# stepper_board.net
KiCad netlist of a schematic drawn in EAGLE
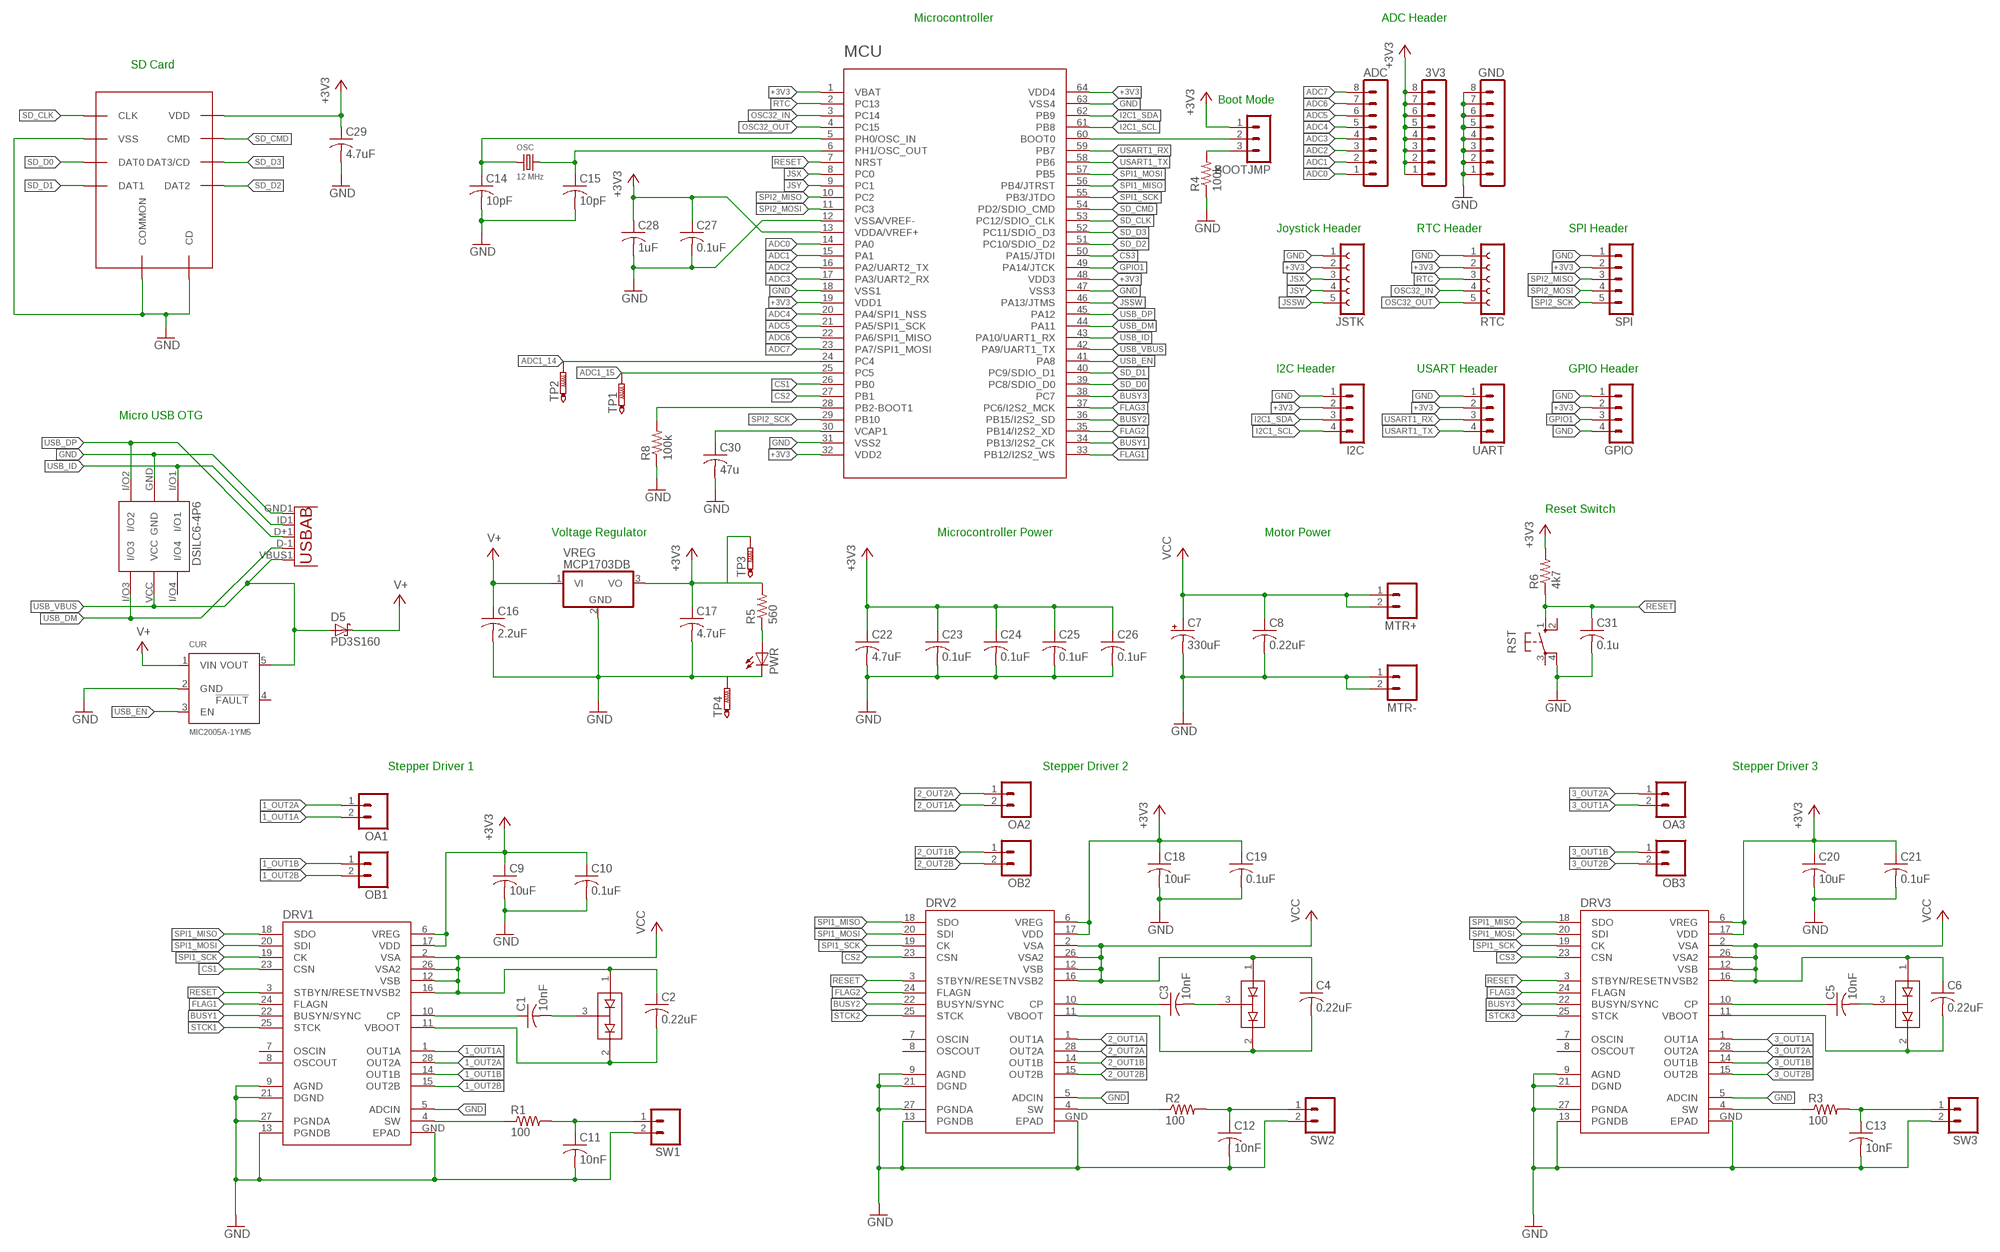
[diagram p0: schematic, sheet 1]

(export (version "E")
  (design (tool "Eeschema 10.0.6"))
  (components
    (comp (ref "3V3")
      (value "MA08-1")
      (footprint "eagle-import:MA08-1")
      (libsource (lib "eagle-import") (part "MA08-1"))
    )
    (comp (ref "ADC")
      (value "MA08-1")
      (footprint "eagle-import:MA08-1")
      (libsource (lib "eagle-import") (part "MA08-1"))
    )
    (comp (ref "BOOTJMP")
      (value "MA03-1")
      (footprint "eagle-import:MA03-1")
      (libsource (lib "eagle-import") (part "MA03-1"))
    )
    (comp (ref "C1")
      (value "10nF")
      (footprint "eagle-import:C0805")
      (libsource (lib "eagle-import") (part "C-USC0805"))
    )
    (comp (ref "C2")
      (value "0.22uF")
      (footprint "eagle-import:C0805")
      (libsource (lib "eagle-import") (part "C-USC0805"))
    )
    (comp (ref "C3")
      (value "10nF")
      (footprint "eagle-import:C0805")
      (libsource (lib "eagle-import") (part "C-USC0805"))
    )
    (comp (ref "C4")
      (value "0.22uF")
      (footprint "eagle-import:C0805")
      (libsource (lib "eagle-import") (part "C-USC0805"))
    )
    (comp (ref "C5")
      (value "10nF")
      (footprint "eagle-import:C0805")
      (libsource (lib "eagle-import") (part "C-USC0805"))
    )
    (comp (ref "C6")
      (value "0.22uF")
      (footprint "eagle-import:C0805")
      (libsource (lib "eagle-import") (part "C-USC0805"))
    )
    (comp (ref "C7")
      (value "330uF")
      (footprint "eagle-import:UD-10X10_NICHICON")
      (libsource (lib "eagle-import") (part "CPOL-USUD-10X10"))
    )
    (comp (ref "C8")
      (value "0.22uF")
      (footprint "eagle-import:C0805")
      (libsource (lib "eagle-import") (part "C-USC0805"))
    )
    (comp (ref "C9")
      (value "10uF")
      (footprint "eagle-import:C0805")
      (libsource (lib "eagle-import") (part "C-USC0805"))
    )
    (comp (ref "C10")
      (value "0.1uF")
      (footprint "eagle-import:C0805")
      (libsource (lib "eagle-import") (part "C-USC0805"))
    )
    (comp (ref "C11")
      (value "10nF")
      (footprint "eagle-import:C0805")
      (libsource (lib "eagle-import") (part "C-USC0805"))
    )
    (comp (ref "C12")
      (value "10nF")
      (footprint "eagle-import:C0805")
      (libsource (lib "eagle-import") (part "C-USC0805"))
    )
    (comp (ref "C13")
      (value "10nF")
      (footprint "eagle-import:C0805")
      (libsource (lib "eagle-import") (part "C-USC0805"))
    )
    (comp (ref "C14")
      (value "10pF")
      (footprint "eagle-import:C0805")
      (libsource (lib "eagle-import") (part "C-USC0805"))
    )
    (comp (ref "C15")
      (value "10pF")
      (footprint "eagle-import:C0805")
      (libsource (lib "eagle-import") (part "C-USC0805"))
    )
    (comp (ref "C16")
      (value "2.2uF")
      (footprint "eagle-import:C0805")
      (libsource (lib "eagle-import") (part "C-USC0805"))
    )
    (comp (ref "C17")
      (value "4.7uF")
      (footprint "eagle-import:C0805")
      (libsource (lib "eagle-import") (part "C-USC0805"))
    )
    (comp (ref "C18")
      (value "10uF")
      (footprint "eagle-import:C0805")
      (libsource (lib "eagle-import") (part "C-USC0805"))
    )
    (comp (ref "C19")
      (value "0.1uF")
      (footprint "eagle-import:C0805")
      (libsource (lib "eagle-import") (part "C-USC0805"))
    )
    (comp (ref "C20")
      (value "10uF")
      (footprint "eagle-import:C0805")
      (libsource (lib "eagle-import") (part "C-USC0805"))
    )
    (comp (ref "C21")
      (value "0.1uF")
      (footprint "eagle-import:C0805")
      (libsource (lib "eagle-import") (part "C-USC0805"))
    )
    (comp (ref "C22")
      (value "4.7uF")
      (footprint "eagle-import:C0805")
      (libsource (lib "eagle-import") (part "C-USC0805"))
    )
    (comp (ref "C23")
      (value "0.1uF")
      (footprint "eagle-import:C0805")
      (libsource (lib "eagle-import") (part "C-USC0805"))
    )
    (comp (ref "C24")
      (value "0.1uF")
      (footprint "eagle-import:C0805")
      (libsource (lib "eagle-import") (part "C-USC0805"))
    )
    (comp (ref "C25")
      (value "0.1uF")
      (footprint "eagle-import:C0805")
      (libsource (lib "eagle-import") (part "C-USC0805"))
    )
    (comp (ref "C26")
      (value "0.1uF")
      (footprint "eagle-import:C0805")
      (libsource (lib "eagle-import") (part "C-USC0805"))
    )
    (comp (ref "C27")
      (value "0.1uF")
      (footprint "eagle-import:C0805")
      (libsource (lib "eagle-import") (part "C-USC0805"))
    )
    (comp (ref "C28")
      (value "1uF")
      (footprint "eagle-import:C0805")
      (libsource (lib "eagle-import") (part "C-USC0805"))
    )
    (comp (ref "C29")
      (value "4.7uF")
      (footprint "eagle-import:C0805")
      (libsource (lib "eagle-import") (part "C-USC0805"))
    )
    (comp (ref "C30")
      (value "47u")
      (footprint "eagle-import:C0805")
      (libsource (lib "eagle-import") (part "C-USC0805"))
    )
    (comp (ref "C31")
      (value "0.1u")
      (footprint "eagle-import:C0805")
      (libsource (lib "eagle-import") (part "C-USC0805"))
    )
    (comp (ref "CUR")
      (value "MIC2005A-1YM5")
      (footprint "eagle-import:SOT23-5")
      (libsource (lib "eagle-import") (part "MIC2005A-1YM5"))
    )
    (comp (ref "D1")
      (value "BAV99")
      (footprint "eagle-import:SOT23")
      (libsource (lib "eagle-import") (part "BAV99"))
    )
    (comp (ref "D2")
      (value "BAV99")
      (footprint "eagle-import:SOT23")
      (libsource (lib "eagle-import") (part "BAV99"))
    )
    (comp (ref "D3")
      (value "BAV99")
      (footprint "eagle-import:SOT23")
      (libsource (lib "eagle-import") (part "BAV99"))
    )
    (comp (ref "D5")
      (value "PD3S160")
      (footprint "eagle-import:POWERDI323")
      (libsource (lib "eagle-import") (part "PD3S160"))
    )
    (comp (ref "DRV1")
      (value "L6470")
      (footprint "eagle-import:HTSSOP28-NOPAD")
      (libsource (lib "eagle-import") (part "L6470"))
    )
    (comp (ref "DRV2")
      (value "L6470")
      (footprint "eagle-import:HTSSOP28-NOPAD")
      (libsource (lib "eagle-import") (part "L6470"))
    )
    (comp (ref "DRV3")
      (value "L6470")
      (footprint "eagle-import:HTSSOP28-NOPAD")
      (libsource (lib "eagle-import") (part "L6470"))
    )
    (comp (ref "ESD")
      (value "DSILC6-4P6")
      (footprint "eagle-import:SOT-666")
      (libsource (lib "eagle-import") (part "DSILC6-4P6"))
    )
    (comp (ref "GND")
      (value "MA08-1")
      (footprint "eagle-import:MA08-1")
      (libsource (lib "eagle-import") (part "MA08-1"))
    )
    (comp (ref "GPIO")
      (value "MA04-1")
      (footprint "eagle-import:MA04-1")
      (libsource (lib "eagle-import") (part "MA04-1"))
    )
    (comp (ref "I2C")
      (value "MA04-1")
      (footprint "eagle-import:MA04-1")
      (libsource (lib "eagle-import") (part "MA04-1"))
    )
    (comp (ref "JSTK")
      (value "FE05-1")
      (footprint "eagle-import:FE05-1")
      (libsource (lib "eagle-import") (part "FE05-1"))
    )
    (comp (ref "MCU")
      (value "STM32F411RE")
      (footprint "eagle-import:TQFP64")
      (libsource (lib "eagle-import") (part "STM32F411RE"))
    )
    (comp (ref "MICROSD")
      (value "SCHA5B0200")
      (footprint "eagle-import:SCHA5B0200")
      (libsource (lib "eagle-import") (part "SCHA5B0200"))
    )
    (comp (ref "MTR+")
      (value "M02")
      (footprint "eagle-import:02P")
      (libsource (lib "eagle-import") (part "M02"))
    )
    (comp (ref "MTR-")
      (value "M02")
      (footprint "eagle-import:02P")
      (libsource (lib "eagle-import") (part "M02"))
    )
    (comp (ref "OA1")
      (value "M02")
      (footprint "eagle-import:02P")
      (libsource (lib "eagle-import") (part "M02"))
    )
    (comp (ref "OA2")
      (value "M02")
      (footprint "eagle-import:02P")
      (libsource (lib "eagle-import") (part "M02"))
    )
    (comp (ref "OA3")
      (value "M02")
      (footprint "eagle-import:02P")
      (libsource (lib "eagle-import") (part "M02"))
    )
    (comp (ref "OB1")
      (value "M02")
      (footprint "eagle-import:02P")
      (libsource (lib "eagle-import") (part "M02"))
    )
    (comp (ref "OB2")
      (value "M02")
      (footprint "eagle-import:02P")
      (libsource (lib "eagle-import") (part "M02"))
    )
    (comp (ref "OB3")
      (value "M02")
      (footprint "eagle-import:02P")
      (libsource (lib "eagle-import") (part "M02"))
    )
    (comp (ref "OSC")
      (value "12 MHz")
      (footprint "eagle-import:3.2X2.5MM")
      (libsource (lib "eagle-import") (part "CRYSTAL.3.2X2.5MM"))
    )
    (comp (ref "PWR")
      (value "LEDCHIP-LED0805")
      (footprint "eagle-import:CHIP-LED0805")
      (libsource (lib "eagle-import") (part "LEDCHIP-LED0805"))
    )
    (comp (ref "R1")
      (value "100")
      (footprint "eagle-import:R0805")
      (libsource (lib "eagle-import") (part "resistor_R-US_R0805"))
    )
    (comp (ref "R2")
      (value "100")
      (footprint "eagle-import:R0805")
      (libsource (lib "eagle-import") (part "resistor_R-US_R0805"))
    )
    (comp (ref "R3")
      (value "100")
      (footprint "eagle-import:R0805")
      (libsource (lib "eagle-import") (part "resistor_R-US_R0805"))
    )
    (comp (ref "R4")
      (value "100k")
      (footprint "eagle-import:R0805")
      (libsource (lib "eagle-import") (part "R-US_R0805"))
    )
    (comp (ref "R5")
      (value "560")
      (footprint "eagle-import:R0805")
      (libsource (lib "eagle-import") (part "R-US_R0805"))
    )
    (comp (ref "R6")
      (value "4k7")
      (footprint "eagle-import:R0805")
      (libsource (lib "eagle-import") (part "R-US_R0805"))
    )
    (comp (ref "R8")
      (value "100k")
      (footprint "eagle-import:R0805")
      (libsource (lib "eagle-import") (part "R-US_R0805"))
    )
    (comp (ref "RST")
      (value "10-XX")
      (footprint "eagle-import:B3F-10XX")
      (fields (field (name "MPN") "B3F-1000"))
      (libsource (lib "eagle-import") (part "10-XX"))
    )
    (comp (ref "RTC")
      (value "FE05-1")
      (footprint "eagle-import:FE05-1")
      (libsource (lib "eagle-import") (part "FE05-1"))
    )
    (comp (ref "SPI")
      (value "MA05-1")
      (footprint "eagle-import:MA05-1")
      (libsource (lib "eagle-import") (part "MA05-1"))
    )
    (comp (ref "SW1")
      (value "M02")
      (footprint "eagle-import:02P")
      (libsource (lib "eagle-import") (part "M02"))
    )
    (comp (ref "SW2")
      (value "M02")
      (footprint "eagle-import:02P")
      (libsource (lib "eagle-import") (part "M02"))
    )
    (comp (ref "SW3")
      (value "M02")
      (footprint "eagle-import:02P")
      (libsource (lib "eagle-import") (part "M02"))
    )
    (comp (ref "TP1")
      (value "PTR1B1,27")
      (footprint "eagle-import:B1,27")
      (libsource (lib "eagle-import") (part "PTR1B1,27"))
    )
    (comp (ref "TP2")
      (value "PTR1B1,27")
      (footprint "eagle-import:B1,27")
      (libsource (lib "eagle-import") (part "PTR1B1,27"))
    )
    (comp (ref "TP3")
      (value "PTR1B1,27")
      (footprint "eagle-import:B1,27")
      (libsource (lib "eagle-import") (part "PTR1B1,27"))
    )
    (comp (ref "TP4")
      (value "PTR1B1,27")
      (footprint "eagle-import:B1,27")
      (libsource (lib "eagle-import") (part "PTR1B1,27"))
    )
    (comp (ref "UART")
      (value "MA04-1")
      (footprint "eagle-import:MA04-1")
      (libsource (lib "eagle-import") (part "MA04-1"))
    )
    (comp (ref "USB")
      (value "USB\"\"")
      (footprint "eagle-import:USB-MICRO-SMD")
      (libsource (lib "eagle-import") (part "USB{dblquote}{dblquote}"))
    )
    (comp (ref "VREG")
      (value "MCP1703DB")
      (footprint "eagle-import:SOT223")
      (libsource (lib "eagle-import") (part "MCP1703DB"))
    )
  )
  (nets
    (net (code "1") (name "+3V3") (class "Default")
      (node (ref "3V3") (pin "1") (pinfunction "1_1") (pintype "passive"))
      (node (ref "3V3") (pin "2") (pinfunction "2_2") (pintype "passive"))
      (node (ref "3V3") (pin "3") (pinfunction "3_3") (pintype "passive"))
      (node (ref "3V3") (pin "4") (pinfunction "4_4") (pintype "passive"))
      (node (ref "3V3") (pin "5") (pinfunction "5_5") (pintype "passive"))
      (node (ref "3V3") (pin "6") (pinfunction "6_6") (pintype "passive"))
      (node (ref "3V3") (pin "7") (pinfunction "7_7") (pintype "passive"))
      (node (ref "3V3") (pin "8") (pinfunction "8_8") (pintype "passive"))
      (node (ref "BOOTJMP") (pin "1") (pinfunction "1_1") (pintype "passive"))
      (node (ref "C10") (pin "1") (pinfunction "1_1") (pintype "passive"))
      (node (ref "C17") (pin "1") (pinfunction "1_1") (pintype "passive"))
      (node (ref "C18") (pin "1") (pinfunction "1_1") (pintype "passive"))
      (node (ref "C19") (pin "1") (pinfunction "1_1") (pintype "passive"))
      (node (ref "C20") (pin "1") (pinfunction "1_1") (pintype "passive"))
      (node (ref "C21") (pin "1") (pinfunction "1_1") (pintype "passive"))
      (node (ref "C22") (pin "1") (pinfunction "1_1") (pintype "passive"))
      (node (ref "C23") (pin "1") (pinfunction "1_1") (pintype "passive"))
      (node (ref "C24") (pin "1") (pinfunction "1_1") (pintype "passive"))
      (node (ref "C25") (pin "1") (pinfunction "1_1") (pintype "passive"))
      (node (ref "C26") (pin "1") (pinfunction "1_1") (pintype "passive"))
      (node (ref "C27") (pin "1") (pinfunction "1_1") (pintype "passive"))
      (node (ref "C28") (pin "1") (pinfunction "1_1") (pintype "passive"))
      (node (ref "C29") (pin "1") (pinfunction "1_1") (pintype "passive"))
      (node (ref "C9") (pin "1") (pinfunction "1_1") (pintype "passive"))
      (node (ref "DRV1") (pin "17") (pinfunction "VDD_17") (pintype "bidirectional"))
      (node (ref "DRV1") (pin "6") (pinfunction "VREG_6") (pintype "bidirectional"))
      (node (ref "DRV2") (pin "17") (pinfunction "VDD_17") (pintype "bidirectional"))
      (node (ref "DRV2") (pin "6") (pinfunction "VREG_6") (pintype "bidirectional"))
      (node (ref "DRV3") (pin "17") (pinfunction "VDD_17") (pintype "bidirectional"))
      (node (ref "DRV3") (pin "6") (pinfunction "VREG_6") (pintype "bidirectional"))
      (node (ref "GPIO") (pin "2") (pinfunction "2_2") (pintype "passive"))
      (node (ref "I2C") (pin "2") (pinfunction "2_2") (pintype "passive"))
      (node (ref "JSTK") (pin "2") (pinfunction "2_2") (pintype "passive"))
      (node (ref "MCU") (pin "1") (pinfunction "VBAT_1") (pintype "bidirectional"))
      (node (ref "MCU") (pin "13") (pinfunction "VDDA/VREF+_13") (pintype "bidirectional"))
      (node (ref "MCU") (pin "19") (pinfunction "VDD1_19") (pintype "bidirectional"))
      (node (ref "MCU") (pin "32") (pinfunction "VDD2_32") (pintype "bidirectional"))
      (node (ref "MCU") (pin "48") (pinfunction "VDD3_48") (pintype "bidirectional"))
      (node (ref "MCU") (pin "64") (pinfunction "VDD4_64") (pintype "bidirectional"))
      (node (ref "MICROSD") (pin "VDD") (pinfunction "VDD_VDD") (pintype "bidirectional"))
      (node (ref "R5") (pin "2") (pinfunction "2_2") (pintype "passive"))
      (node (ref "R6") (pin "2") (pinfunction "2_2") (pintype "passive"))
      (node (ref "RTC") (pin "2") (pinfunction "2_2") (pintype "passive"))
      (node (ref "SPI") (pin "2") (pinfunction "2_2") (pintype "passive"))
      (node (ref "TP3") (pin "TP") (pinfunction "TP_TP") (pintype "input"))
      (node (ref "UART") (pin "2") (pinfunction "2_2") (pintype "passive"))
      (node (ref "VREG") (pin "3") (pinfunction "VO_3") (pintype "passive"))
    )
    (net (code "2") (name "1_OUT1A") (class "Default")
      (node (ref "DRV1") (pin "1") (pinfunction "OUT1A_1") (pintype "bidirectional"))
      (node (ref "OA1") (pin "2") (pinfunction "2_2") (pintype "passive"))
    )
    (net (code "3") (name "1_OUT1B") (class "Default")
      (node (ref "DRV1") (pin "14") (pinfunction "OUT1B_14") (pintype "bidirectional"))
      (node (ref "OB1") (pin "1") (pinfunction "1_1") (pintype "passive"))
    )
    (net (code "4") (name "1_OUT2A") (class "Default")
      (node (ref "DRV1") (pin "28") (pinfunction "OUT2A_28") (pintype "bidirectional"))
      (node (ref "OA1") (pin "1") (pinfunction "1_1") (pintype "passive"))
    )
    (net (code "5") (name "1_OUT2B") (class "Default")
      (node (ref "DRV1") (pin "15") (pinfunction "OUT2B_15") (pintype "bidirectional"))
      (node (ref "OB1") (pin "2") (pinfunction "2_2") (pintype "passive"))
    )
    (net (code "6") (name "2_OUT1A") (class "Default")
      (node (ref "DRV2") (pin "1") (pinfunction "OUT1A_1") (pintype "bidirectional"))
      (node (ref "OA2") (pin "2") (pinfunction "2_2") (pintype "passive"))
    )
    (net (code "7") (name "2_OUT1B") (class "Default")
      (node (ref "DRV2") (pin "14") (pinfunction "OUT1B_14") (pintype "bidirectional"))
      (node (ref "OB2") (pin "1") (pinfunction "1_1") (pintype "passive"))
    )
    (net (code "8") (name "2_OUT2A") (class "Default")
      (node (ref "DRV2") (pin "28") (pinfunction "OUT2A_28") (pintype "bidirectional"))
      (node (ref "OA2") (pin "1") (pinfunction "1_1") (pintype "passive"))
    )
    (net (code "9") (name "2_OUT2B") (class "Default")
      (node (ref "DRV2") (pin "15") (pinfunction "OUT2B_15") (pintype "bidirectional"))
      (node (ref "OB2") (pin "2") (pinfunction "2_2") (pintype "passive"))
    )
    (net (code "10") (name "3_OUT1A") (class "Default")
      (node (ref "DRV3") (pin "1") (pinfunction "OUT1A_1") (pintype "bidirectional"))
      (node (ref "OA3") (pin "2") (pinfunction "2_2") (pintype "passive"))
    )
    (net (code "11") (name "3_OUT1B") (class "Default")
      (node (ref "DRV3") (pin "14") (pinfunction "OUT1B_14") (pintype "bidirectional"))
      (node (ref "OB3") (pin "1") (pinfunction "1_1") (pintype "passive"))
    )
    (net (code "12") (name "3_OUT2A") (class "Default")
      (node (ref "DRV3") (pin "28") (pinfunction "OUT2A_28") (pintype "bidirectional"))
      (node (ref "OA3") (pin "1") (pinfunction "1_1") (pintype "passive"))
    )
    (net (code "13") (name "3_OUT2B") (class "Default")
      (node (ref "DRV3") (pin "15") (pinfunction "OUT2B_15") (pintype "bidirectional"))
      (node (ref "OB3") (pin "2") (pinfunction "2_2") (pintype "passive"))
    )
    (net (code "14") (name "ADC0") (class "Default")
      (node (ref "ADC") (pin "1") (pinfunction "1_1") (pintype "passive"))
      (node (ref "MCU") (pin "14") (pinfunction "PA0_14") (pintype "bidirectional"))
    )
    (net (code "15") (name "ADC1") (class "Default")
      (node (ref "ADC") (pin "2") (pinfunction "2_2") (pintype "passive"))
      (node (ref "MCU") (pin "15") (pinfunction "PA1_15") (pintype "bidirectional"))
    )
    (net (code "16") (name "ADC1_14") (class "Default")
      (node (ref "MCU") (pin "24") (pinfunction "PC4_24") (pintype "bidirectional"))
      (node (ref "TP2") (pin "TP") (pinfunction "TP_TP") (pintype "input"))
    )
    (net (code "17") (name "ADC1_15") (class "Default")
      (node (ref "MCU") (pin "25") (pinfunction "PC5_25") (pintype "bidirectional"))
      (node (ref "TP1") (pin "TP") (pinfunction "TP_TP") (pintype "input"))
    )
    (net (code "18") (name "ADC2") (class "Default")
      (node (ref "ADC") (pin "3") (pinfunction "3_3") (pintype "passive"))
      (node (ref "MCU") (pin "16") (pinfunction "PA2/UART2_TX_16") (pintype "bidirectional"))
    )
    (net (code "19") (name "ADC3") (class "Default")
      (node (ref "ADC") (pin "4") (pinfunction "4_4") (pintype "passive"))
      (node (ref "MCU") (pin "17") (pinfunction "PA3/UART2_RX_17") (pintype "bidirectional"))
    )
    (net (code "20") (name "ADC4") (class "Default")
      (node (ref "ADC") (pin "5") (pinfunction "5_5") (pintype "passive"))
      (node (ref "MCU") (pin "20") (pinfunction "PA4/SPI1_NSS_20") (pintype "bidirectional"))
    )
    (net (code "21") (name "ADC5") (class "Default")
      (node (ref "ADC") (pin "6") (pinfunction "6_6") (pintype "passive"))
      (node (ref "MCU") (pin "21") (pinfunction "PA5/SPI1_SCK_21") (pintype "bidirectional"))
    )
    (net (code "22") (name "ADC6") (class "Default")
      (node (ref "ADC") (pin "7") (pinfunction "7_7") (pintype "passive"))
      (node (ref "MCU") (pin "22") (pinfunction "PA6/SPI1_MISO_22") (pintype "bidirectional"))
    )
    (net (code "23") (name "ADC7") (class "Default")
      (node (ref "ADC") (pin "8") (pinfunction "8_8") (pintype "passive"))
      (node (ref "MCU") (pin "23") (pinfunction "PA7/SPI1_MOSI_23") (pintype "bidirectional"))
    )
    (net (code "24") (name "BUSY1") (class "Default")
      (node (ref "DRV1") (pin "22") (pinfunction "BUSYN/SYNC_22") (pintype "bidirectional"))
      (node (ref "MCU") (pin "34") (pinfunction "PB13/I2S2_CK_34") (pintype "bidirectional"))
    )
    (net (code "25") (name "BUSY2") (class "Default")
      (node (ref "DRV2") (pin "22") (pinfunction "BUSYN/SYNC_22") (pintype "bidirectional"))
      (node (ref "MCU") (pin "36") (pinfunction "PB15/I2S2_SD_36") (pintype "bidirectional"))
    )
    (net (code "26") (name "BUSY3") (class "Default")
      (node (ref "DRV3") (pin "22") (pinfunction "BUSYN/SYNC_22") (pintype "bidirectional"))
      (node (ref "MCU") (pin "38") (pinfunction "PC7_38") (pintype "bidirectional"))
    )
    (net (code "27") (name "CS1") (class "Default")
      (node (ref "DRV1") (pin "23") (pinfunction "CSN_23") (pintype "bidirectional"))
      (node (ref "MCU") (pin "26") (pinfunction "PB0_26") (pintype "bidirectional"))
    )
    (net (code "28") (name "CS2") (class "Default")
      (node (ref "DRV2") (pin "23") (pinfunction "CSN_23") (pintype "bidirectional"))
      (node (ref "MCU") (pin "27") (pinfunction "PB1_27") (pintype "bidirectional"))
    )
    (net (code "29") (name "CS3") (class "Default")
      (node (ref "DRV3") (pin "23") (pinfunction "CSN_23") (pintype "bidirectional"))
      (node (ref "MCU") (pin "50") (pinfunction "PA15/JTDI_50") (pintype "bidirectional"))
    )
    (net (code "30") (name "FLAG1") (class "Default")
      (node (ref "DRV1") (pin "24") (pinfunction "FLAGN_24") (pintype "bidirectional"))
      (node (ref "MCU") (pin "33") (pinfunction "PB12/I2S2_WS_33") (pintype "bidirectional"))
    )
    (net (code "31") (name "FLAG2") (class "Default")
      (node (ref "DRV2") (pin "24") (pinfunction "FLAGN_24") (pintype "bidirectional"))
      (node (ref "MCU") (pin "35") (pinfunction "PB14/I2S2_XD_35") (pintype "bidirectional"))
    )
    (net (code "32") (name "FLAG3") (class "Default")
      (node (ref "DRV3") (pin "24") (pinfunction "FLAGN_24") (pintype "bidirectional"))
      (node (ref "MCU") (pin "37") (pinfunction "PC6/I2S2_MCK_37") (pintype "bidirectional"))
    )
    (net (code "33") (name "GND") (class "Default")
      (node (ref "C10") (pin "2") (pinfunction "2_2") (pintype "passive"))
      (node (ref "C11") (pin "2") (pinfunction "2_2") (pintype "passive"))
      (node (ref "C12") (pin "2") (pinfunction "2_2") (pintype "passive"))
      (node (ref "C13") (pin "2") (pinfunction "2_2") (pintype "passive"))
      (node (ref "C14") (pin "2") (pinfunction "2_2") (pintype "passive"))
      (node (ref "C15") (pin "2") (pinfunction "2_2") (pintype "passive"))
      (node (ref "C16") (pin "2") (pinfunction "2_2") (pintype "passive"))
      (node (ref "C17") (pin "2") (pinfunction "2_2") (pintype "passive"))
      (node (ref "C18") (pin "2") (pinfunction "2_2") (pintype "passive"))
      (node (ref "C19") (pin "2") (pinfunction "2_2") (pintype "passive"))
      (node (ref "C20") (pin "2") (pinfunction "2_2") (pintype "passive"))
      (node (ref "C21") (pin "2") (pinfunction "2_2") (pintype "passive"))
      (node (ref "C22") (pin "2") (pinfunction "2_2") (pintype "passive"))
      (node (ref "C23") (pin "2") (pinfunction "2_2") (pintype "passive"))
      (node (ref "C24") (pin "2") (pinfunction "2_2") (pintype "passive"))
      (node (ref "C25") (pin "2") (pinfunction "2_2") (pintype "passive"))
      (node (ref "C26") (pin "2") (pinfunction "2_2") (pintype "passive"))
      (node (ref "C27") (pin "2") (pinfunction "2_2") (pintype "passive"))
      (node (ref "C28") (pin "2") (pinfunction "2_2") (pintype "passive"))
      (node (ref "C29") (pin "2") (pinfunction "2_2") (pintype "passive"))
      (node (ref "C30") (pin "2") (pinfunction "2_2") (pintype "passive"))
      (node (ref "C31") (pin "2") (pinfunction "2_2") (pintype "passive"))
      (node (ref "C7") (pin "-") (pinfunction "-_-") (pintype "passive"))
      (node (ref "C8") (pin "2") (pinfunction "2_2") (pintype "passive"))
      (node (ref "C9") (pin "2") (pinfunction "2_2") (pintype "passive"))
      (node (ref "CUR") (pin "2") (pinfunction "GND_2") (pintype "power_in"))
      (node (ref "DRV1") (pin "13") (pinfunction "PGNDB_13") (pintype "bidirectional"))
      (node (ref "DRV1") (pin "21") (pinfunction "DGND_21") (pintype "bidirectional"))
      (node (ref "DRV1") (pin "27") (pinfunction "PGNDA_27") (pintype "bidirectional"))
      (node (ref "DRV1") (pin "5") (pinfunction "ADCIN_5") (pintype "bidirectional"))
      (node (ref "DRV1") (pin "9") (pinfunction "AGND_9") (pintype "bidirectional"))
      (node (ref "DRV1") (pin "GND") (pinfunction "EPAD_GND") (pintype "bidirectional"))
      (node (ref "DRV2") (pin "13") (pinfunction "PGNDB_13") (pintype "bidirectional"))
      (node (ref "DRV2") (pin "21") (pinfunction "DGND_21") (pintype "bidirectional"))
      (node (ref "DRV2") (pin "27") (pinfunction "PGNDA_27") (pintype "bidirectional"))
      (node (ref "DRV2") (pin "5") (pinfunction "ADCIN_5") (pintype "bidirectional"))
      (node (ref "DRV2") (pin "9") (pinfunction "AGND_9") (pintype "bidirectional"))
      (node (ref "DRV2") (pin "GND") (pinfunction "EPAD_GND") (pintype "bidirectional"))
      (node (ref "DRV3") (pin "13") (pinfunction "PGNDB_13") (pintype "bidirectional"))
      (node (ref "DRV3") (pin "21") (pinfunction "DGND_21") (pintype "bidirectional"))
      (node (ref "DRV3") (pin "27") (pinfunction "PGNDA_27") (pintype "bidirectional"))
      (node (ref "DRV3") (pin "5") (pinfunction "ADCIN_5") (pintype "bidirectional"))
      (node (ref "DRV3") (pin "9") (pinfunction "AGND_9") (pintype "bidirectional"))
      (node (ref "DRV3") (pin "GND") (pinfunction "EPAD_GND") (pintype "bidirectional"))
      (node (ref "ESD") (pin "GND") (pinfunction "GND_GND") (pintype "bidirectional"))
      (node (ref "GND") (pin "1") (pinfunction "1_1") (pintype "passive"))
      (node (ref "GND") (pin "2") (pinfunction "2_2") (pintype "passive"))
      (node (ref "GND") (pin "3") (pinfunction "3_3") (pintype "passive"))
      (node (ref "GND") (pin "4") (pinfunction "4_4") (pintype "passive"))
      (node (ref "GND") (pin "5") (pinfunction "5_5") (pintype "passive"))
      (node (ref "GND") (pin "6") (pinfunction "6_6") (pintype "passive"))
      (node (ref "GND") (pin "7") (pinfunction "7_7") (pintype "passive"))
      (node (ref "GND") (pin "8") (pinfunction "8_8") (pintype "passive"))
      (node (ref "GPIO") (pin "1") (pinfunction "1_1") (pintype "passive"))
      (node (ref "GPIO") (pin "4") (pinfunction "4_4") (pintype "passive"))
      (node (ref "I2C") (pin "1") (pinfunction "1_1") (pintype "passive"))
      (node (ref "JSTK") (pin "1") (pinfunction "1_1") (pintype "passive"))
      (node (ref "MCU") (pin "12") (pinfunction "VSSA/VREF-_12") (pintype "bidirectional"))
      (node (ref "MCU") (pin "18") (pinfunction "VSS1_18") (pintype "bidirectional"))
      (node (ref "MCU") (pin "31") (pinfunction "VSS2_31") (pintype "bidirectional"))
      (node (ref "MCU") (pin "47") (pinfunction "VSS3_47") (pintype "bidirectional"))
      (node (ref "MCU") (pin "63") (pinfunction "VSS4_63") (pintype "bidirectional"))
      (node (ref "MICROSD") (pin "CD_SW") (pinfunction "CD_CD_SW") (pintype "bidirectional"))
      (node (ref "MICROSD") (pin "COMMON") (pinfunction "COMMON_COMMON") (pintype "bidirectional"))
      (node (ref "MICROSD") (pin "VSS") (pinfunction "VSS_VSS") (pintype "bidirectional"))
      (node (ref "MTR-") (pin "1") (pinfunction "1_1") (pintype "passive"))
      (node (ref "MTR-") (pin "2") (pinfunction "2_2") (pintype "passive"))
      (node (ref "PWR") (pin "C") (pinfunction "C_C") (pintype "passive"))
      (node (ref "R4") (pin "1") (pinfunction "1_1") (pintype "passive"))
      (node (ref "R8") (pin "1") (pinfunction "1_1") (pintype "passive"))
      (node (ref "RST") (pin "4") (pinfunction "P1_4") (pintype "passive"))
      (node (ref "RTC") (pin "1") (pinfunction "1_1") (pintype "passive"))
      (node (ref "SPI") (pin "1") (pinfunction "1_1") (pintype "passive"))
      (node (ref "SW1") (pin "2") (pinfunction "2_2") (pintype "passive"))
      (node (ref "SW2") (pin "2") (pinfunction "2_2") (pintype "passive"))
      (node (ref "SW3") (pin "2") (pinfunction "2_2") (pintype "passive"))
      (node (ref "TP4") (pin "TP") (pinfunction "TP_TP") (pintype "input"))
      (node (ref "UART") (pin "1") (pinfunction "1_1") (pintype "passive"))
      (node (ref "USB") (pin "GND1") (pinfunction "GND_GND1") (pintype "bidirectional"))
      (node (ref "VREG") (pin "2") (pinfunction "GND_2") (pintype "passive"))
    )
    (net (code "34") (name "GPIO1") (class "Default")
      (node (ref "GPIO") (pin "3") (pinfunction "3_3") (pintype "passive"))
      (node (ref "MCU") (pin "49") (pinfunction "PA14/JTCK_49") (pintype "bidirectional"))
    )
    (net (code "35") (name "I2C1_SCL") (class "Default")
      (node (ref "I2C") (pin "4") (pinfunction "4_4") (pintype "passive"))
      (node (ref "MCU") (pin "61") (pinfunction "PB8_61") (pintype "bidirectional"))
    )
    (net (code "36") (name "I2C1_SDA") (class "Default")
      (node (ref "I2C") (pin "3") (pinfunction "3_3") (pintype "passive"))
      (node (ref "MCU") (pin "62") (pinfunction "PB9_62") (pintype "bidirectional"))
    )
    (net (code "37") (name "JSSW") (class "Default")
      (node (ref "JSTK") (pin "5") (pinfunction "5_5") (pintype "passive"))
      (node (ref "MCU") (pin "46") (pinfunction "PA13/JTMS_46") (pintype "bidirectional"))
    )
    (net (code "38") (name "JSX") (class "Default")
      (node (ref "JSTK") (pin "3") (pinfunction "3_3") (pintype "passive"))
      (node (ref "MCU") (pin "8") (pinfunction "PC0_8") (pintype "bidirectional"))
    )
    (net (code "39") (name "JSY") (class "Default")
      (node (ref "JSTK") (pin "4") (pinfunction "4_4") (pintype "passive"))
      (node (ref "MCU") (pin "9") (pinfunction "PC1_9") (pintype "bidirectional"))
    )
    (net (code "40") (name "Net-(BOOTJMP-Pad3)") (class "Default")
      (node (ref "BOOTJMP") (pin "3") (pinfunction "3_3") (pintype "passive"))
      (node (ref "R4") (pin "2") (pinfunction "2_2") (pintype "passive"))
    )
    (net (code "41") (name "Net-(C11-Pad1)") (class "Default")
      (node (ref "C11") (pin "1") (pinfunction "1_1") (pintype "passive"))
      (node (ref "R1") (pin "2") (pinfunction "2_2") (pintype "passive"))
      (node (ref "SW1") (pin "1") (pinfunction "1_1") (pintype "passive"))
    )
    (net (code "42") (name "Net-(C12-Pad1)") (class "Default")
      (node (ref "C12") (pin "1") (pinfunction "1_1") (pintype "passive"))
      (node (ref "R2") (pin "2") (pinfunction "2_2") (pintype "passive"))
      (node (ref "SW2") (pin "1") (pinfunction "1_1") (pintype "passive"))
    )
    (net (code "43") (name "Net-(C13-Pad1)") (class "Default")
      (node (ref "C13") (pin "1") (pinfunction "1_1") (pintype "passive"))
      (node (ref "R3") (pin "2") (pinfunction "2_2") (pintype "passive"))
      (node (ref "SW3") (pin "1") (pinfunction "1_1") (pintype "passive"))
    )
    (net (code "44") (name "Net-(D1-C2)") (class "Default")
      (node (ref "C2") (pin "2") (pinfunction "2_2") (pintype "passive"))
      (node (ref "D1") (pin "2") (pinfunction "C2_2") (pintype "bidirectional"))
      (node (ref "DRV1") (pin "11") (pinfunction "VBOOT_11") (pintype "bidirectional"))
    )
    (net (code "45") (name "Net-(D1-COM)") (class "Default")
      (node (ref "C1") (pin "2") (pinfunction "2_2") (pintype "passive"))
      (node (ref "D1") (pin "3") (pinfunction "COM_3") (pintype "bidirectional"))
    )
    (net (code "46") (name "Net-(D2-C2)") (class "Default")
      (node (ref "C4") (pin "2") (pinfunction "2_2") (pintype "passive"))
      (node (ref "D2") (pin "2") (pinfunction "C2_2") (pintype "bidirectional"))
      (node (ref "DRV2") (pin "11") (pinfunction "VBOOT_11") (pintype "bidirectional"))
    )
    (net (code "47") (name "Net-(D2-COM)") (class "Default")
      (node (ref "C3") (pin "2") (pinfunction "2_2") (pintype "passive"))
      (node (ref "D2") (pin "3") (pinfunction "COM_3") (pintype "bidirectional"))
    )
    (net (code "48") (name "Net-(D3-C2)") (class "Default")
      (node (ref "C6") (pin "2") (pinfunction "2_2") (pintype "passive"))
      (node (ref "D3") (pin "2") (pinfunction "C2_2") (pintype "bidirectional"))
      (node (ref "DRV3") (pin "11") (pinfunction "VBOOT_11") (pintype "bidirectional"))
    )
    (net (code "49") (name "Net-(D3-COM)") (class "Default")
      (node (ref "C5") (pin "2") (pinfunction "2_2") (pintype "passive"))
      (node (ref "D3") (pin "3") (pinfunction "COM_3") (pintype "bidirectional"))
    )
    (net (code "50") (name "Net-(DRV1-CP)") (class "Default")
      (node (ref "C1") (pin "1") (pinfunction "1_1") (pintype "passive"))
      (node (ref "DRV1") (pin "10") (pinfunction "CP_10") (pintype "bidirectional"))
    )
    (net (code "51") (name "Net-(DRV1-SW)") (class "Default")
      (node (ref "DRV1") (pin "4") (pinfunction "SW_4") (pintype "bidirectional"))
      (node (ref "R1") (pin "1") (pinfunction "1_1") (pintype "passive"))
    )
    (net (code "52") (name "Net-(DRV2-CP)") (class "Default")
      (node (ref "C3") (pin "1") (pinfunction "1_1") (pintype "passive"))
      (node (ref "DRV2") (pin "10") (pinfunction "CP_10") (pintype "bidirectional"))
    )
    (net (code "53") (name "Net-(DRV2-SW)") (class "Default")
      (node (ref "DRV2") (pin "4") (pinfunction "SW_4") (pintype "bidirectional"))
      (node (ref "R2") (pin "1") (pinfunction "1_1") (pintype "passive"))
    )
    (net (code "54") (name "Net-(DRV3-CP)") (class "Default")
      (node (ref "C5") (pin "1") (pinfunction "1_1") (pintype "passive"))
      (node (ref "DRV3") (pin "10") (pinfunction "CP_10") (pintype "bidirectional"))
    )
    (net (code "55") (name "Net-(DRV3-SW)") (class "Default")
      (node (ref "DRV3") (pin "4") (pinfunction "SW_4") (pintype "bidirectional"))
      (node (ref "R3") (pin "1") (pinfunction "1_1") (pintype "passive"))
    )
    (net (code "56") (name "Net-(MCU-BOOT0)") (class "Default")
      (node (ref "BOOTJMP") (pin "2") (pinfunction "2_2") (pintype "passive"))
      (node (ref "MCU") (pin "60") (pinfunction "BOOT0_60") (pintype "bidirectional"))
    )
    (net (code "57") (name "Net-(MCU-PB2-BOOT1)") (class "Default")
      (node (ref "MCU") (pin "28") (pinfunction "PB2-BOOT1_28") (pintype "bidirectional"))
      (node (ref "R8") (pin "2") (pinfunction "2_2") (pintype "passive"))
    )
    (net (code "58") (name "Net-(MCU-PH0{slash}OSC_IN)") (class "Default")
      (node (ref "C14") (pin "1") (pinfunction "1_1") (pintype "passive"))
      (node (ref "MCU") (pin "5") (pinfunction "PH0/OSC_IN_5") (pintype "bidirectional"))
      (node (ref "OSC") (pin "1") (pinfunction "1_1") (pintype "passive"))
    )
    (net (code "59") (name "Net-(MCU-PH1{slash}OSC_OUT)") (class "Default")
      (node (ref "C15") (pin "1") (pinfunction "1_1") (pintype "passive"))
      (node (ref "MCU") (pin "6") (pinfunction "PH1/OSC_OUT_6") (pintype "bidirectional"))
      (node (ref "OSC") (pin "3") (pinfunction "2_3") (pintype "passive"))
    )
    (net (code "60") (name "Net-(MCU-VCAP1)") (class "Default")
      (node (ref "C30") (pin "1") (pinfunction "1_1") (pintype "passive"))
      (node (ref "MCU") (pin "30") (pinfunction "VCAP1_30") (pintype "bidirectional"))
    )
    (net (code "61") (name "Net-(PWR-PadA)") (class "Default")
      (node (ref "PWR") (pin "A") (pinfunction "A_A") (pintype "passive"))
      (node (ref "R5") (pin "1") (pinfunction "1_1") (pintype "passive"))
    )
    (net (code "62") (name "OSC32_IN") (class "Default")
      (node (ref "MCU") (pin "3") (pinfunction "PC14_3") (pintype "bidirectional"))
      (node (ref "RTC") (pin "4") (pinfunction "4_4") (pintype "passive"))
    )
    (net (code "63") (name "OSC32_OUT") (class "Default")
      (node (ref "MCU") (pin "4") (pinfunction "PC15_4") (pintype "bidirectional"))
      (node (ref "RTC") (pin "5") (pinfunction "5_5") (pintype "passive"))
    )
    (net (code "64") (name "RESET") (class "Default")
      (node (ref "C31") (pin "1") (pinfunction "1_1") (pintype "passive"))
      (node (ref "DRV1") (pin "3") (pinfunction "STBYN/RESETN_3") (pintype "bidirectional"))
      (node (ref "DRV2") (pin "3") (pinfunction "STBYN/RESETN_3") (pintype "bidirectional"))
      (node (ref "DRV3") (pin "3") (pinfunction "STBYN/RESETN_3") (pintype "bidirectional"))
      (node (ref "MCU") (pin "7") (pinfunction "NRST_7") (pintype "bidirectional"))
      (node (ref "R6") (pin "1") (pinfunction "1_1") (pintype "passive"))
      (node (ref "RST") (pin "1") (pinfunction "S_1") (pintype "passive"))
    )
    (net (code "65") (name "RTC") (class "Default")
      (node (ref "MCU") (pin "2") (pinfunction "PC13_2") (pintype "bidirectional"))
      (node (ref "RTC") (pin "3") (pinfunction "3_3") (pintype "passive"))
    )
    (net (code "66") (name "SD_CLK") (class "Default")
      (node (ref "MCU") (pin "53") (pinfunction "PC12/SDIO_CLK_53") (pintype "bidirectional"))
      (node (ref "MICROSD") (pin "CLK") (pinfunction "CLK_CLK") (pintype "bidirectional"))
    )
    (net (code "67") (name "SD_CMD") (class "Default")
      (node (ref "MCU") (pin "54") (pinfunction "PD2/SDIO_CMD_54") (pintype "bidirectional"))
      (node (ref "MICROSD") (pin "CMD") (pinfunction "CMD_CMD") (pintype "bidirectional"))
    )
    (net (code "68") (name "SD_D0") (class "Default")
      (node (ref "MCU") (pin "39") (pinfunction "PC8/SDIO_D0_39") (pintype "bidirectional"))
      (node (ref "MICROSD") (pin "DAT0") (pinfunction "DAT0_DAT0") (pintype "bidirectional"))
    )
    (net (code "69") (name "SD_D1") (class "Default")
      (node (ref "MCU") (pin "40") (pinfunction "PC9/SDIO_D1_40") (pintype "bidirectional"))
      (node (ref "MICROSD") (pin "DAT1") (pinfunction "DAT1_DAT1") (pintype "bidirectional"))
    )
    (net (code "70") (name "SD_D2") (class "Default")
      (node (ref "MCU") (pin "51") (pinfunction "PC10/SDIO_D2_51") (pintype "bidirectional"))
      (node (ref "MICROSD") (pin "DAT2") (pinfunction "DAT2_DAT2") (pintype "bidirectional"))
    )
    (net (code "71") (name "SD_D3") (class "Default")
      (node (ref "MCU") (pin "52") (pinfunction "PC11/SDIO_D3_52") (pintype "bidirectional"))
      (node (ref "MICROSD") (pin "DAT3/CD") (pinfunction "DAT3/CD_DAT3/CD") (pintype "bidirectional"))
    )
    (net (code "72") (name "SPI1_MISO") (class "Default")
      (node (ref "DRV1") (pin "18") (pinfunction "SDO_18") (pintype "bidirectional"))
      (node (ref "DRV2") (pin "18") (pinfunction "SDO_18") (pintype "bidirectional"))
      (node (ref "DRV3") (pin "18") (pinfunction "SDO_18") (pintype "bidirectional"))
      (node (ref "MCU") (pin "56") (pinfunction "PB4/JTRST_56") (pintype "bidirectional"))
    )
    (net (code "73") (name "SPI1_MOSI") (class "Default")
      (node (ref "DRV1") (pin "20") (pinfunction "SDI_20") (pintype "bidirectional"))
      (node (ref "DRV2") (pin "20") (pinfunction "SDI_20") (pintype "bidirectional"))
      (node (ref "DRV3") (pin "20") (pinfunction "SDI_20") (pintype "bidirectional"))
      (node (ref "MCU") (pin "57") (pinfunction "PB5_57") (pintype "bidirectional"))
    )
    (net (code "74") (name "SPI1_SCK") (class "Default")
      (node (ref "DRV1") (pin "19") (pinfunction "CK_19") (pintype "bidirectional"))
      (node (ref "DRV2") (pin "19") (pinfunction "CK_19") (pintype "bidirectional"))
      (node (ref "DRV3") (pin "19") (pinfunction "CK_19") (pintype "bidirectional"))
      (node (ref "MCU") (pin "55") (pinfunction "PB3/JTDO_55") (pintype "bidirectional"))
    )
    (net (code "75") (name "SPI2_MISO") (class "Default")
      (node (ref "MCU") (pin "10") (pinfunction "PC2_10") (pintype "bidirectional"))
      (node (ref "SPI") (pin "3") (pinfunction "3_3") (pintype "passive"))
    )
    (net (code "76") (name "SPI2_MOSI") (class "Default")
      (node (ref "MCU") (pin "11") (pinfunction "PC3_11") (pintype "bidirectional"))
      (node (ref "SPI") (pin "4") (pinfunction "4_4") (pintype "passive"))
    )
    (net (code "77") (name "SPI2_SCK") (class "Default")
      (node (ref "MCU") (pin "29") (pinfunction "PB10_29") (pintype "bidirectional"))
      (node (ref "SPI") (pin "5") (pinfunction "5_5") (pintype "passive"))
    )
    (net (code "78") (name "STCK1") (class "Default")
      (node (ref "DRV1") (pin "25") (pinfunction "STCK_25") (pintype "bidirectional"))
    )
    (net (code "79") (name "STCK2") (class "Default")
      (node (ref "DRV2") (pin "25") (pinfunction "STCK_25") (pintype "bidirectional"))
    )
    (net (code "80") (name "STCK3") (class "Default")
      (node (ref "DRV3") (pin "25") (pinfunction "STCK_25") (pintype "bidirectional"))
    )
    (net (code "81") (name "USART1_RX") (class "Default")
      (node (ref "MCU") (pin "59") (pinfunction "PB7_59") (pintype "bidirectional"))
      (node (ref "UART") (pin "3") (pinfunction "3_3") (pintype "passive"))
    )
    (net (code "82") (name "USART1_TX") (class "Default")
      (node (ref "MCU") (pin "58") (pinfunction "PB6_58") (pintype "bidirectional"))
      (node (ref "UART") (pin "4") (pinfunction "4_4") (pintype "passive"))
    )
    (net (code "83") (name "USB_DM") (class "Default")
      (node (ref "ESD") (pin "I/O3") (pinfunction "I/O3_I/O3") (pintype "bidirectional"))
      (node (ref "MCU") (pin "44") (pinfunction "PA11_44") (pintype "bidirectional"))
      (node (ref "USB") (pin "D-1") (pinfunction "D-_D-1") (pintype "bidirectional"))
    )
    (net (code "84") (name "USB_DP") (class "Default")
      (node (ref "ESD") (pin "I/O2") (pinfunction "I/O2_I/O2") (pintype "bidirectional"))
      (node (ref "MCU") (pin "45") (pinfunction "PA12_45") (pintype "bidirectional"))
      (node (ref "USB") (pin "D+1") (pinfunction "D+_D+1") (pintype "bidirectional"))
    )
    (net (code "85") (name "USB_EN") (class "Default")
      (node (ref "CUR") (pin "3") (pinfunction "EN_3") (pintype "input"))
      (node (ref "MCU") (pin "41") (pinfunction "PA8_41") (pintype "bidirectional"))
    )
    (net (code "86") (name "USB_ID") (class "Default")
      (node (ref "ESD") (pin "I/O1") (pinfunction "I/O1_I/O1") (pintype "bidirectional"))
      (node (ref "MCU") (pin "43") (pinfunction "PA10/UART1_RX_43") (pintype "bidirectional"))
      (node (ref "USB") (pin "ID1") (pinfunction "USBID_ID1") (pintype "bidirectional"))
    )
    (net (code "87") (name "USB_VBUS") (class "Default")
      (node (ref "CUR") (pin "5") (pinfunction "VOUT_5") (pintype "output"))
      (node (ref "D5") (pin "A") (pinfunction "A_A") (pintype "passive"))
      (node (ref "ESD") (pin "VCC") (pinfunction "VCC_VCC") (pintype "bidirectional"))
      (node (ref "MCU") (pin "42") (pinfunction "PA9/UART1_TX_42") (pintype "bidirectional"))
      (node (ref "USB") (pin "VBUS1") (pinfunction "VBUS_VBUS1") (pintype "bidirectional"))
    )
    (net (code "88") (name "V+") (class "Default")
      (node (ref "C16") (pin "1") (pinfunction "1_1") (pintype "passive"))
      (node (ref "CUR") (pin "1") (pinfunction "VIN_1") (pintype "power_in"))
      (node (ref "D5") (pin "C") (pinfunction "C_C") (pintype "passive"))
      (node (ref "VREG") (pin "1") (pinfunction "VI_1") (pintype "input"))
    )
    (net (code "89") (name "VCC") (class "Default")
      (node (ref "C2") (pin "1") (pinfunction "1_1") (pintype "passive"))
      (node (ref "C4") (pin "1") (pinfunction "1_1") (pintype "passive"))
      (node (ref "C6") (pin "1") (pinfunction "1_1") (pintype "passive"))
      (node (ref "C7") (pin "+") (pinfunction "+_+") (pintype "passive"))
      (node (ref "C8") (pin "1") (pinfunction "1_1") (pintype "passive"))
      (node (ref "D1") (pin "1") (pinfunction "A1_1") (pintype "bidirectional"))
      (node (ref "D2") (pin "1") (pinfunction "A1_1") (pintype "bidirectional"))
      (node (ref "D3") (pin "1") (pinfunction "A1_1") (pintype "bidirectional"))
      (node (ref "DRV1") (pin "12") (pinfunction "VSB_12") (pintype "bidirectional"))
      (node (ref "DRV1") (pin "16") (pinfunction "VSB2_16") (pintype "bidirectional"))
      (node (ref "DRV1") (pin "2") (pinfunction "VSA_2") (pintype "bidirectional"))
      (node (ref "DRV1") (pin "26") (pinfunction "VSA2_26") (pintype "bidirectional"))
      (node (ref "DRV2") (pin "12") (pinfunction "VSB_12") (pintype "bidirectional"))
      (node (ref "DRV2") (pin "16") (pinfunction "VSB2_16") (pintype "bidirectional"))
      (node (ref "DRV2") (pin "2") (pinfunction "VSA_2") (pintype "bidirectional"))
      (node (ref "DRV2") (pin "26") (pinfunction "VSA2_26") (pintype "bidirectional"))
      (node (ref "DRV3") (pin "12") (pinfunction "VSB_12") (pintype "bidirectional"))
      (node (ref "DRV3") (pin "16") (pinfunction "VSB2_16") (pintype "bidirectional"))
      (node (ref "DRV3") (pin "2") (pinfunction "VSA_2") (pintype "bidirectional"))
      (node (ref "DRV3") (pin "26") (pinfunction "VSA2_26") (pintype "bidirectional"))
      (node (ref "MTR+") (pin "1") (pinfunction "1_1") (pintype "passive"))
      (node (ref "MTR+") (pin "2") (pinfunction "2_2") (pintype "passive"))
    )
    (net (code "90") (name "unconnected-(CUR-~{FAULT}-Pad4)") (class "Default")
      (node (ref "CUR") (pin "4") (pinfunction "~{FAULT}_4") (pintype "output"))
    )
    (net (code "91") (name "unconnected-(DRV1-OSCIN-Pad7)") (class "Default")
      (node (ref "DRV1") (pin "7") (pinfunction "OSCIN_7") (pintype "bidirectional"))
    )
    (net (code "92") (name "unconnected-(DRV1-OSCOUT-Pad8)") (class "Default")
      (node (ref "DRV1") (pin "8") (pinfunction "OSCOUT_8") (pintype "bidirectional"))
    )
    (net (code "93") (name "unconnected-(DRV2-OSCIN-Pad7)") (class "Default")
      (node (ref "DRV2") (pin "7") (pinfunction "OSCIN_7") (pintype "bidirectional"))
    )
    (net (code "94") (name "unconnected-(DRV2-OSCOUT-Pad8)") (class "Default")
      (node (ref "DRV2") (pin "8") (pinfunction "OSCOUT_8") (pintype "bidirectional"))
    )
    (net (code "95") (name "unconnected-(DRV3-OSCIN-Pad7)") (class "Default")
      (node (ref "DRV3") (pin "7") (pinfunction "OSCIN_7") (pintype "bidirectional"))
    )
    (net (code "96") (name "unconnected-(DRV3-OSCOUT-Pad8)") (class "Default")
      (node (ref "DRV3") (pin "8") (pinfunction "OSCOUT_8") (pintype "bidirectional"))
    )
    (net (code "97") (name "unconnected-(ESD-PadI{slash}O4)") (class "Default")
      (node (ref "ESD") (pin "I/O4") (pinfunction "I/O4_I/O4") (pintype "bidirectional"))
    )
    (net (code "98") (name "unconnected-(RST-P-Pad3)") (class "Default")
      (node (ref "RST") (pin "3") (pinfunction "P_3") (pintype "passive"))
    )
    (net (code "99") (name "unconnected-(RST-S1-Pad2)") (class "Default")
      (node (ref "RST") (pin "2") (pinfunction "S1_2") (pintype "passive"))
    )
  )
)
